# RFM50_Breakout_3.net
KiCad netlist of a schematic drawn in EAGLE
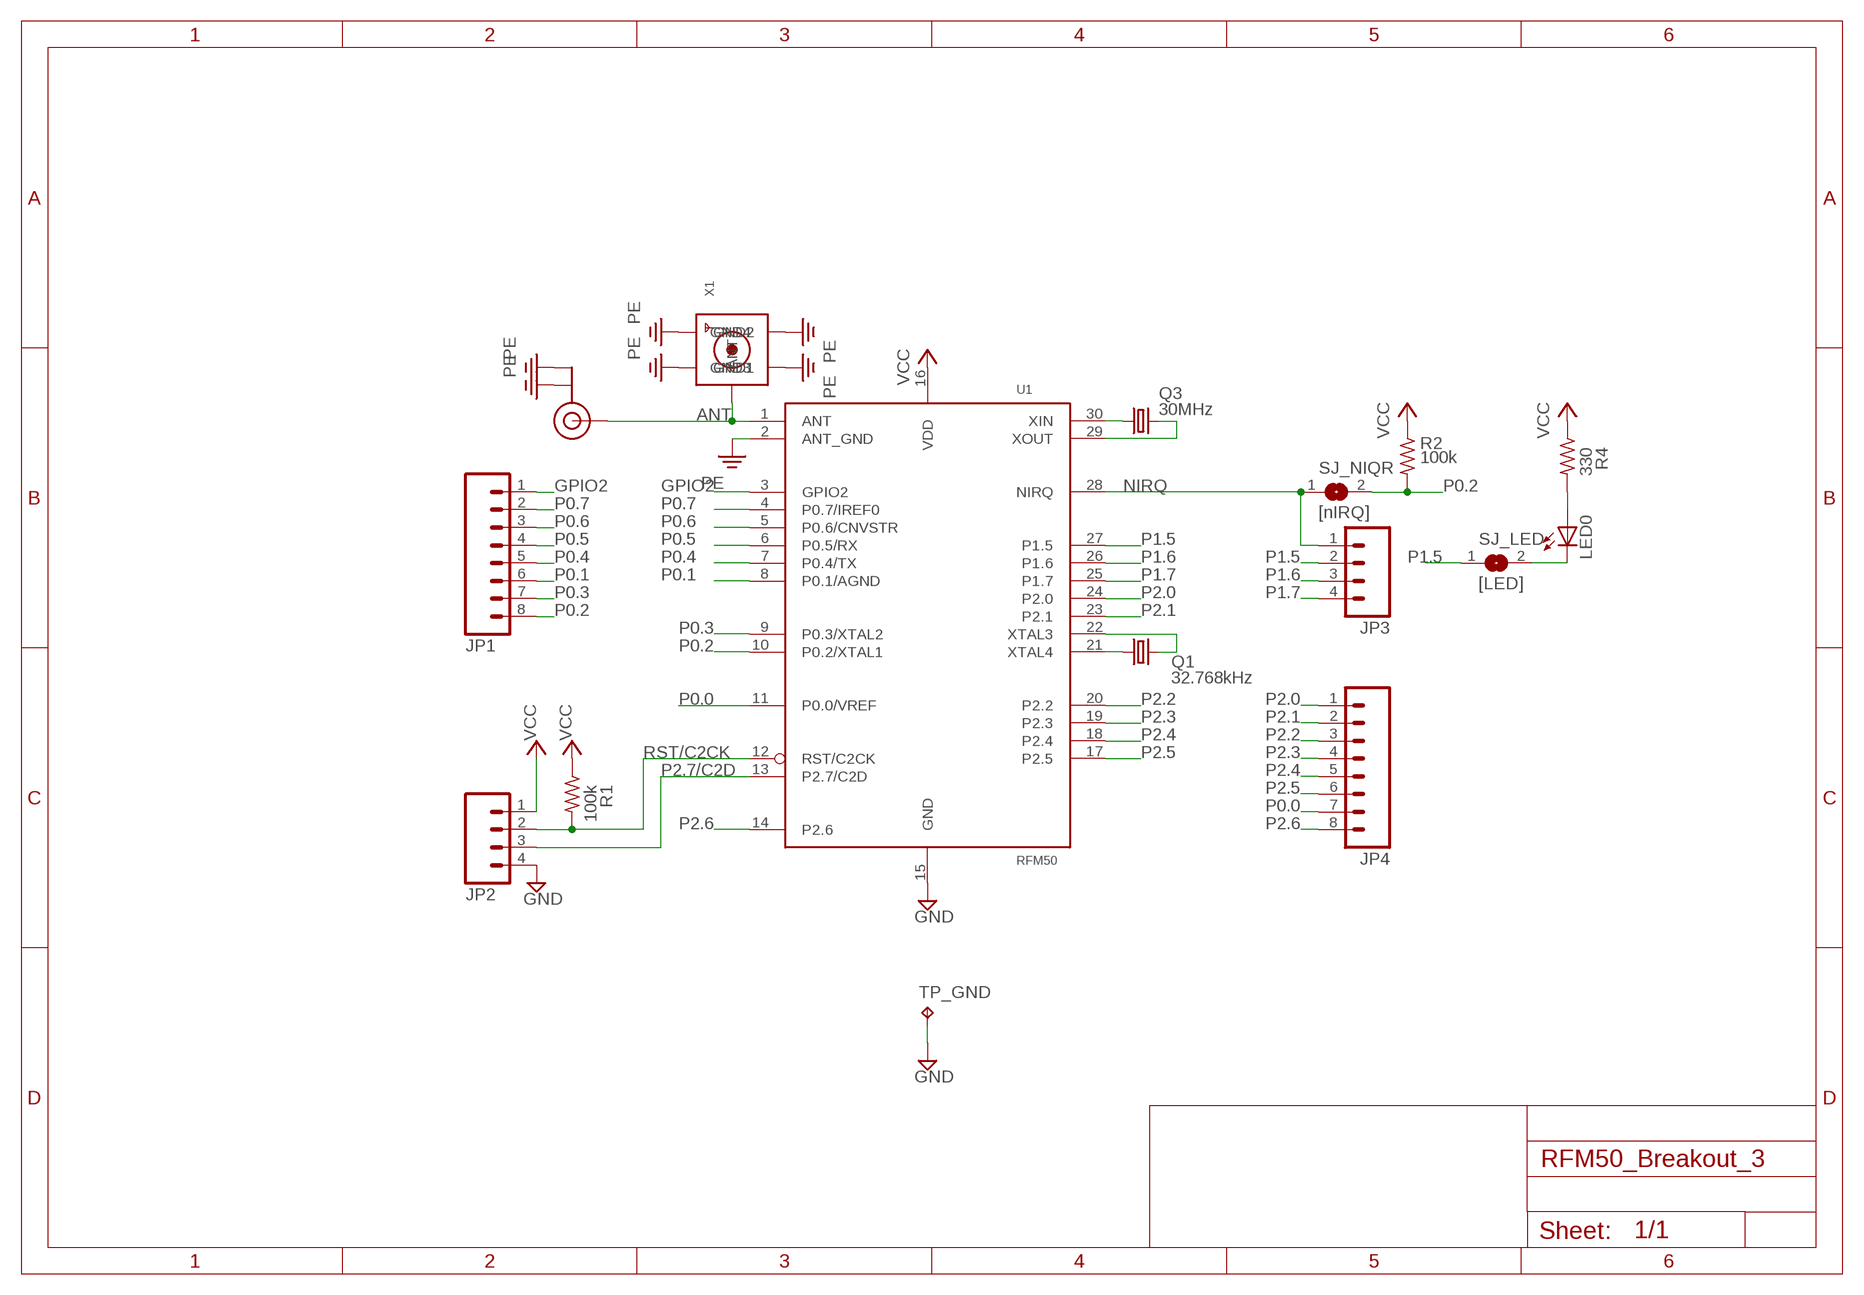
[diagram p0: schematic, sheet 1]

(export (version "E")
  (design (tool "Eeschema 10.0.6"))
  (components
    (comp (ref "JP1")
      (value "M081X08")
      (footprint "eagle-import:1X08")
      (libsource (lib "eagle-import") (part "M081X08"))
    )
    (comp (ref "JP2")
      (value "M04PTH")
      (footprint "eagle-import:1X04")
      (libsource (lib "eagle-import") (part "M04PTH"))
    )
    (comp (ref "JP3")
      (value "M04PTH")
      (footprint "eagle-import:1X04")
      (libsource (lib "eagle-import") (part "M04PTH"))
    )
    (comp (ref "JP4")
      (value "M081X08")
      (footprint "eagle-import:1X08")
      (libsource (lib "eagle-import") (part "M081X08"))
    )
    (comp (ref "LED0")
      (value "LED3MM")
      (footprint "eagle-import:LED3MM")
      (libsource (lib "eagle-import") (part "LED3MM"))
    )
    (comp (ref "Q1")
      (value "32.768kHz")
      (footprint "eagle-import:TC26H")
      (libsource (lib "eagle-import") (part "CRYSTALTC26H"))
    )
    (comp (ref "Q3")
      (value "30MHz")
      (footprint "eagle-import:HC49_S")
      (libsource (lib "eagle-import") (part "CRYSTALHC49S"))
    )
    (comp (ref "R1")
      (value "100k")
      (footprint "eagle-import:RCL_0204_7")
      (libsource (lib "eagle-import") (part "RCL_R-US_0204/7"))
    )
    (comp (ref "R2")
      (value "100k")
      (footprint "eagle-import:RCL_M1206")
      (libsource (lib "eagle-import") (part "RCL_R-US_M1206"))
    )
    (comp (ref "R4")
      (value "330")
      (footprint "eagle-import:RCL_0204_5")
      (libsource (lib "eagle-import") (part "RCL_R-US_0204/5"))
    )
    (comp (ref "SJ_LED")
      (value "[LED]")
      (footprint "eagle-import:SOLDERJUMPER_REFLOW")
      (libsource (lib "eagle-import") (part "SOLDERJUMPERREFLOW"))
    )
    (comp (ref "SJ_NIQR")
      (value "[nIRQ]")
      (footprint "eagle-import:SOLDERJUMPER_REFLOW")
      (libsource (lib "eagle-import") (part "SOLDERJUMPERREFLOW"))
    )
    (comp (ref "TP_GND")
      (value "TPPAD1-10")
      (footprint "eagle-import:P1-10_TP")
      (libsource (lib "eagle-import") (part "TPPAD1-10"))
    )
    (comp (ref "U$1")
      (value "U.FL")
      (footprint "eagle-import:U.FL")
      (libsource (lib "eagle-import") (part "U.FL"))
    )
    (comp (ref "U1")
      (value "RFM50")
      (footprint "eagle-import:RFM50")
      (libsource (lib "eagle-import") (part "RFM50"))
    )
    (comp (ref "X1")
      (value "SMACONNECTOR")
      (footprint "eagle-import:SMA90_DIP")
      (libsource (lib "eagle-import") (part "SMACONNECTOR"))
    )
  )
  (nets
    (net (code "1") (name "/ANT") (class "Default")
      (node (ref "U$1") (pin "P$3") (pinfunction "SIGNAL_P$3") (pintype "bidirectional"))
      (node (ref "U1") (pin "1") (pinfunction "ANT_1") (pintype "bidirectional"))
      (node (ref "X1") (pin "ANTENNA") (pinfunction "ANT_ANTENNA") (pintype "bidirectional"))
    )
    (net (code "2") (name "/GPIO2") (class "Default")
      (node (ref "JP1") (pin "1") (pinfunction "1_1") (pintype "passive"))
      (node (ref "U1") (pin "3") (pinfunction "GPIO2_3") (pintype "bidirectional"))
    )
    (net (code "3") (name "/NIRQ") (class "Default")
      (node (ref "JP3") (pin "1") (pinfunction "1_1") (pintype "passive"))
      (node (ref "SJ_NIQR") (pin "1") (pinfunction "1_1") (pintype "passive"))
      (node (ref "U1") (pin "28") (pinfunction "NIRQ_28") (pintype "output"))
    )
    (net (code "4") (name "/P0.0") (class "Default")
      (node (ref "JP4") (pin "7") (pinfunction "7_7") (pintype "passive"))
      (node (ref "U1") (pin "11") (pinfunction "P0.0/VREF_11") (pintype "bidirectional"))
    )
    (net (code "5") (name "/P0.1") (class "Default")
      (node (ref "JP1") (pin "6") (pinfunction "6_6") (pintype "passive"))
      (node (ref "U1") (pin "8") (pinfunction "P0.1/AGND_8") (pintype "bidirectional"))
    )
    (net (code "6") (name "/P0.2") (class "Default")
      (node (ref "JP1") (pin "8") (pinfunction "8_8") (pintype "passive"))
      (node (ref "R2") (pin "2") (pinfunction "2_2") (pintype "passive"))
      (node (ref "SJ_NIQR") (pin "2") (pinfunction "2_2") (pintype "passive"))
      (node (ref "U1") (pin "10") (pinfunction "P0.2/XTAL1_10") (pintype "bidirectional"))
    )
    (net (code "7") (name "/P0.3") (class "Default")
      (node (ref "JP1") (pin "7") (pinfunction "7_7") (pintype "passive"))
      (node (ref "U1") (pin "9") (pinfunction "P0.3/XTAL2_9") (pintype "bidirectional"))
    )
    (net (code "8") (name "/P0.4") (class "Default")
      (node (ref "JP1") (pin "5") (pinfunction "5_5") (pintype "passive"))
      (node (ref "U1") (pin "7") (pinfunction "P0.4/TX_7") (pintype "bidirectional"))
    )
    (net (code "9") (name "/P0.5") (class "Default")
      (node (ref "JP1") (pin "4") (pinfunction "4_4") (pintype "passive"))
      (node (ref "U1") (pin "6") (pinfunction "P0.5/RX_6") (pintype "bidirectional"))
    )
    (net (code "10") (name "/P0.6") (class "Default")
      (node (ref "JP1") (pin "3") (pinfunction "3_3") (pintype "passive"))
      (node (ref "U1") (pin "5") (pinfunction "P0.6/CNVSTR_5") (pintype "bidirectional"))
    )
    (net (code "11") (name "/P0.7") (class "Default")
      (node (ref "JP1") (pin "2") (pinfunction "2_2") (pintype "passive"))
      (node (ref "U1") (pin "4") (pinfunction "P0.7/IREF0_4") (pintype "bidirectional"))
    )
    (net (code "12") (name "/P1.5") (class "Default")
      (node (ref "JP3") (pin "2") (pinfunction "2_2") (pintype "passive"))
      (node (ref "SJ_LED") (pin "1") (pinfunction "1_1") (pintype "passive"))
      (node (ref "U1") (pin "27") (pinfunction "P1.5_27") (pintype "bidirectional"))
    )
    (net (code "13") (name "/P1.6") (class "Default")
      (node (ref "JP3") (pin "3") (pinfunction "3_3") (pintype "passive"))
      (node (ref "U1") (pin "26") (pinfunction "P1.6_26") (pintype "bidirectional"))
    )
    (net (code "14") (name "/P1.7") (class "Default")
      (node (ref "JP3") (pin "4") (pinfunction "4_4") (pintype "passive"))
      (node (ref "U1") (pin "25") (pinfunction "P1.7_25") (pintype "bidirectional"))
    )
    (net (code "15") (name "/P2.0") (class "Default")
      (node (ref "JP4") (pin "1") (pinfunction "1_1") (pintype "passive"))
      (node (ref "U1") (pin "24") (pinfunction "P2.0_24") (pintype "bidirectional"))
    )
    (net (code "16") (name "/P2.1") (class "Default")
      (node (ref "JP4") (pin "2") (pinfunction "2_2") (pintype "passive"))
      (node (ref "U1") (pin "23") (pinfunction "P2.1_23") (pintype "bidirectional"))
    )
    (net (code "17") (name "/P2.2") (class "Default")
      (node (ref "JP4") (pin "3") (pinfunction "3_3") (pintype "passive"))
      (node (ref "U1") (pin "20") (pinfunction "P2.2_20") (pintype "bidirectional"))
    )
    (net (code "18") (name "/P2.3") (class "Default")
      (node (ref "JP4") (pin "4") (pinfunction "4_4") (pintype "passive"))
      (node (ref "U1") (pin "19") (pinfunction "P2.3_19") (pintype "bidirectional"))
    )
    (net (code "19") (name "/P2.4") (class "Default")
      (node (ref "JP4") (pin "5") (pinfunction "5_5") (pintype "passive"))
      (node (ref "U1") (pin "18") (pinfunction "P2.4_18") (pintype "bidirectional"))
    )
    (net (code "20") (name "/P2.5") (class "Default")
      (node (ref "JP4") (pin "6") (pinfunction "6_6") (pintype "passive"))
      (node (ref "U1") (pin "17") (pinfunction "P2.5_17") (pintype "bidirectional"))
    )
    (net (code "21") (name "/P2.6") (class "Default")
      (node (ref "JP4") (pin "8") (pinfunction "8_8") (pintype "passive"))
      (node (ref "U1") (pin "14") (pinfunction "P2.6_14") (pintype "bidirectional"))
    )
    (net (code "22") (name "/P2.7{slash}C2D") (class "Default")
      (node (ref "JP2") (pin "3") (pinfunction "3_3") (pintype "passive"))
      (node (ref "U1") (pin "13") (pinfunction "P2.7/C2D_13") (pintype "bidirectional"))
    )
    (net (code "23") (name "/RST{slash}C2CK") (class "Default")
      (node (ref "JP2") (pin "2") (pinfunction "2_2") (pintype "passive"))
      (node (ref "R1") (pin "2") (pinfunction "2_2") (pintype "passive"))
      (node (ref "U1") (pin "12") (pinfunction "RST/C2CK_12") (pintype "bidirectional"))
    )
    (net (code "24") (name "GND") (class "Default")
      (node (ref "JP2") (pin "4") (pinfunction "4_4") (pintype "passive"))
      (node (ref "TP_GND") (pin "TP") (pinfunction "TP_TP") (pintype "input"))
      (node (ref "U1") (pin "15") (pinfunction "GND_15") (pintype "bidirectional"))
    )
    (net (code "25") (name "Net-(LED0-C)") (class "Default")
      (node (ref "LED0") (pin "K") (pinfunction "C_K") (pintype "passive"))
      (node (ref "SJ_LED") (pin "2") (pinfunction "2_2") (pintype "passive"))
    )
    (net (code "26") (name "Net-(LED0-PadA)") (class "Default")
      (node (ref "LED0") (pin "A") (pinfunction "A_A") (pintype "passive"))
      (node (ref "R4") (pin "2") (pinfunction "2_2") (pintype "passive"))
    )
    (net (code "27") (name "Net-(U1-XIN)") (class "Default")
      (node (ref "Q3") (pin "1") (pinfunction "1_1") (pintype "passive"))
      (node (ref "U1") (pin "30") (pinfunction "XIN_30") (pintype "input"))
    )
    (net (code "28") (name "Net-(U1-XOUT)") (class "Default")
      (node (ref "Q3") (pin "2") (pinfunction "2_2") (pintype "passive"))
      (node (ref "U1") (pin "29") (pinfunction "XOUT_29") (pintype "output"))
    )
    (net (code "29") (name "Net-(U1-XTAL3)") (class "Default")
      (node (ref "Q1") (pin "2") (pinfunction "2_2") (pintype "passive"))
      (node (ref "U1") (pin "22") (pinfunction "XTAL3_22") (pintype "bidirectional"))
    )
    (net (code "30") (name "Net-(U1-XTAL4)") (class "Default")
      (node (ref "Q1") (pin "1") (pinfunction "1_1") (pintype "passive"))
      (node (ref "U1") (pin "21") (pinfunction "XTAL4_21") (pintype "bidirectional"))
    )
    (net (code "31") (name "PE") (class "Default")
      (node (ref "U$1") (pin "P$1") (pinfunction "GND_P$1") (pintype "bidirectional"))
      (node (ref "U$1") (pin "P$2") (pinfunction "GND_P$2") (pintype "bidirectional"))
      (node (ref "U1") (pin "2") (pinfunction "ANT_GND_2") (pintype "bidirectional"))
      (node (ref "X1") (pin "GND1") (pinfunction "GND1_GND1") (pintype "power_in"))
      (node (ref "X1") (pin "GND2") (pinfunction "GND2_GND2") (pintype "power_in"))
      (node (ref "X1") (pin "GND3") (pinfunction "GND3_GND3") (pintype "power_in"))
      (node (ref "X1") (pin "GND4") (pinfunction "GND4_GND4") (pintype "power_in"))
    )
    (net (code "32") (name "VCC") (class "Default")
      (node (ref "JP2") (pin "1") (pinfunction "1_1") (pintype "passive"))
      (node (ref "R1") (pin "1") (pinfunction "1_1") (pintype "passive"))
      (node (ref "R2") (pin "1") (pinfunction "1_1") (pintype "passive"))
      (node (ref "R4") (pin "1") (pinfunction "1_1") (pintype "passive"))
      (node (ref "U1") (pin "16") (pinfunction "VDD_16") (pintype "power_in"))
    )
  )
)
